# PumpSpark.net
KiCad netlist of a schematic drawn in EAGLE
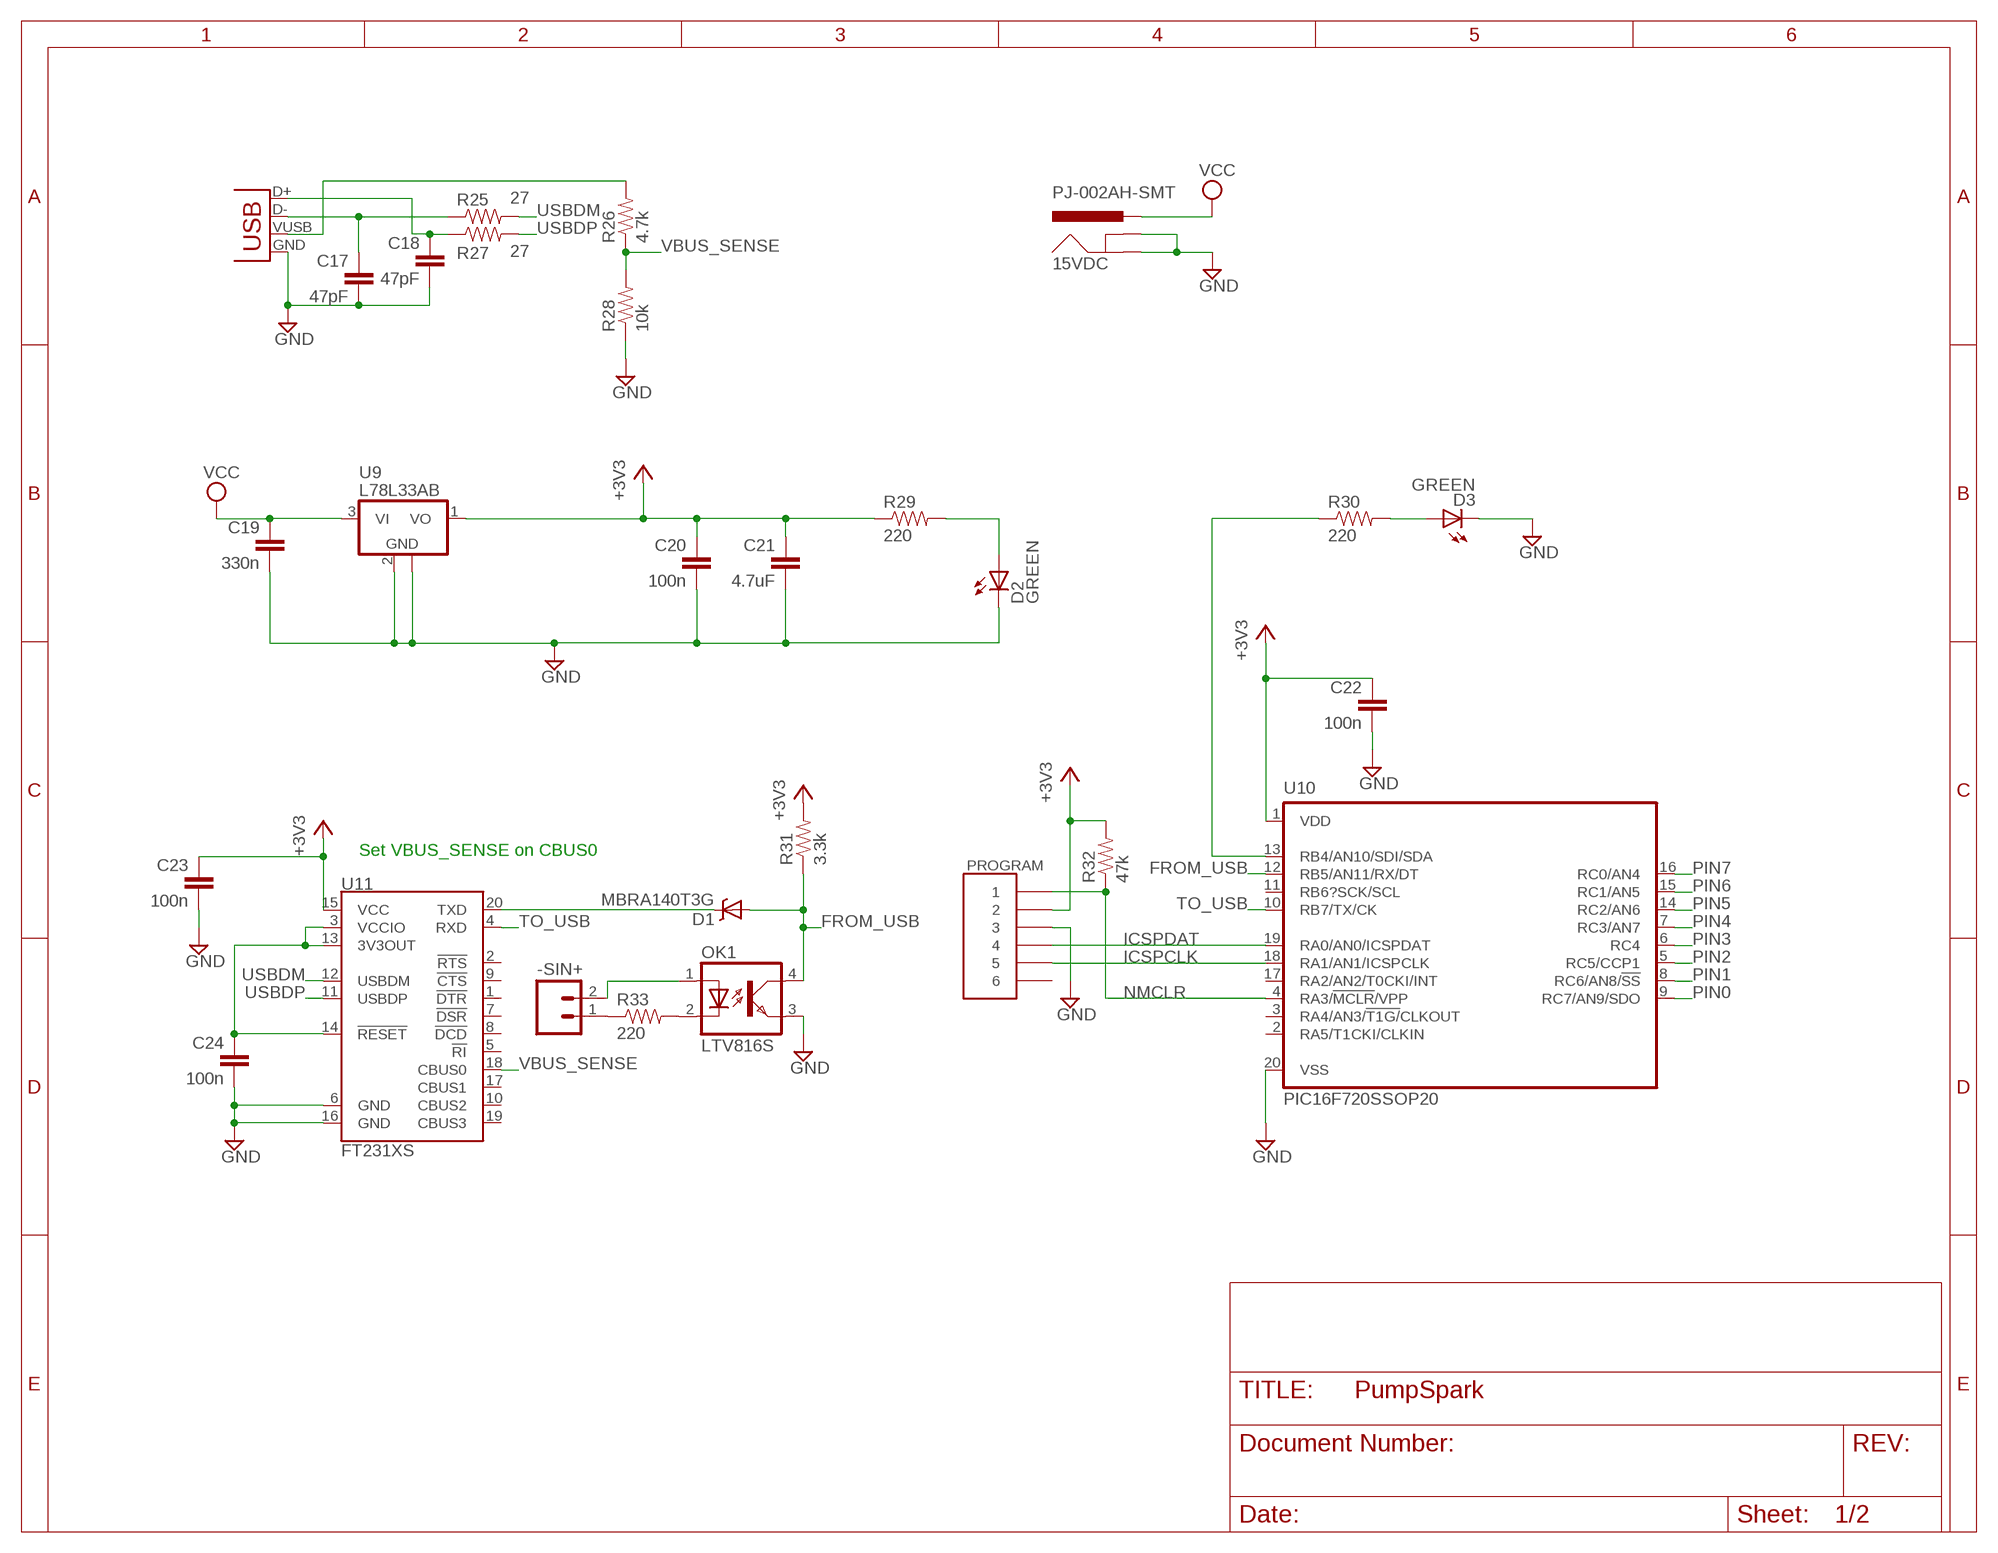
[diagram p0: schematic, sheet 1]
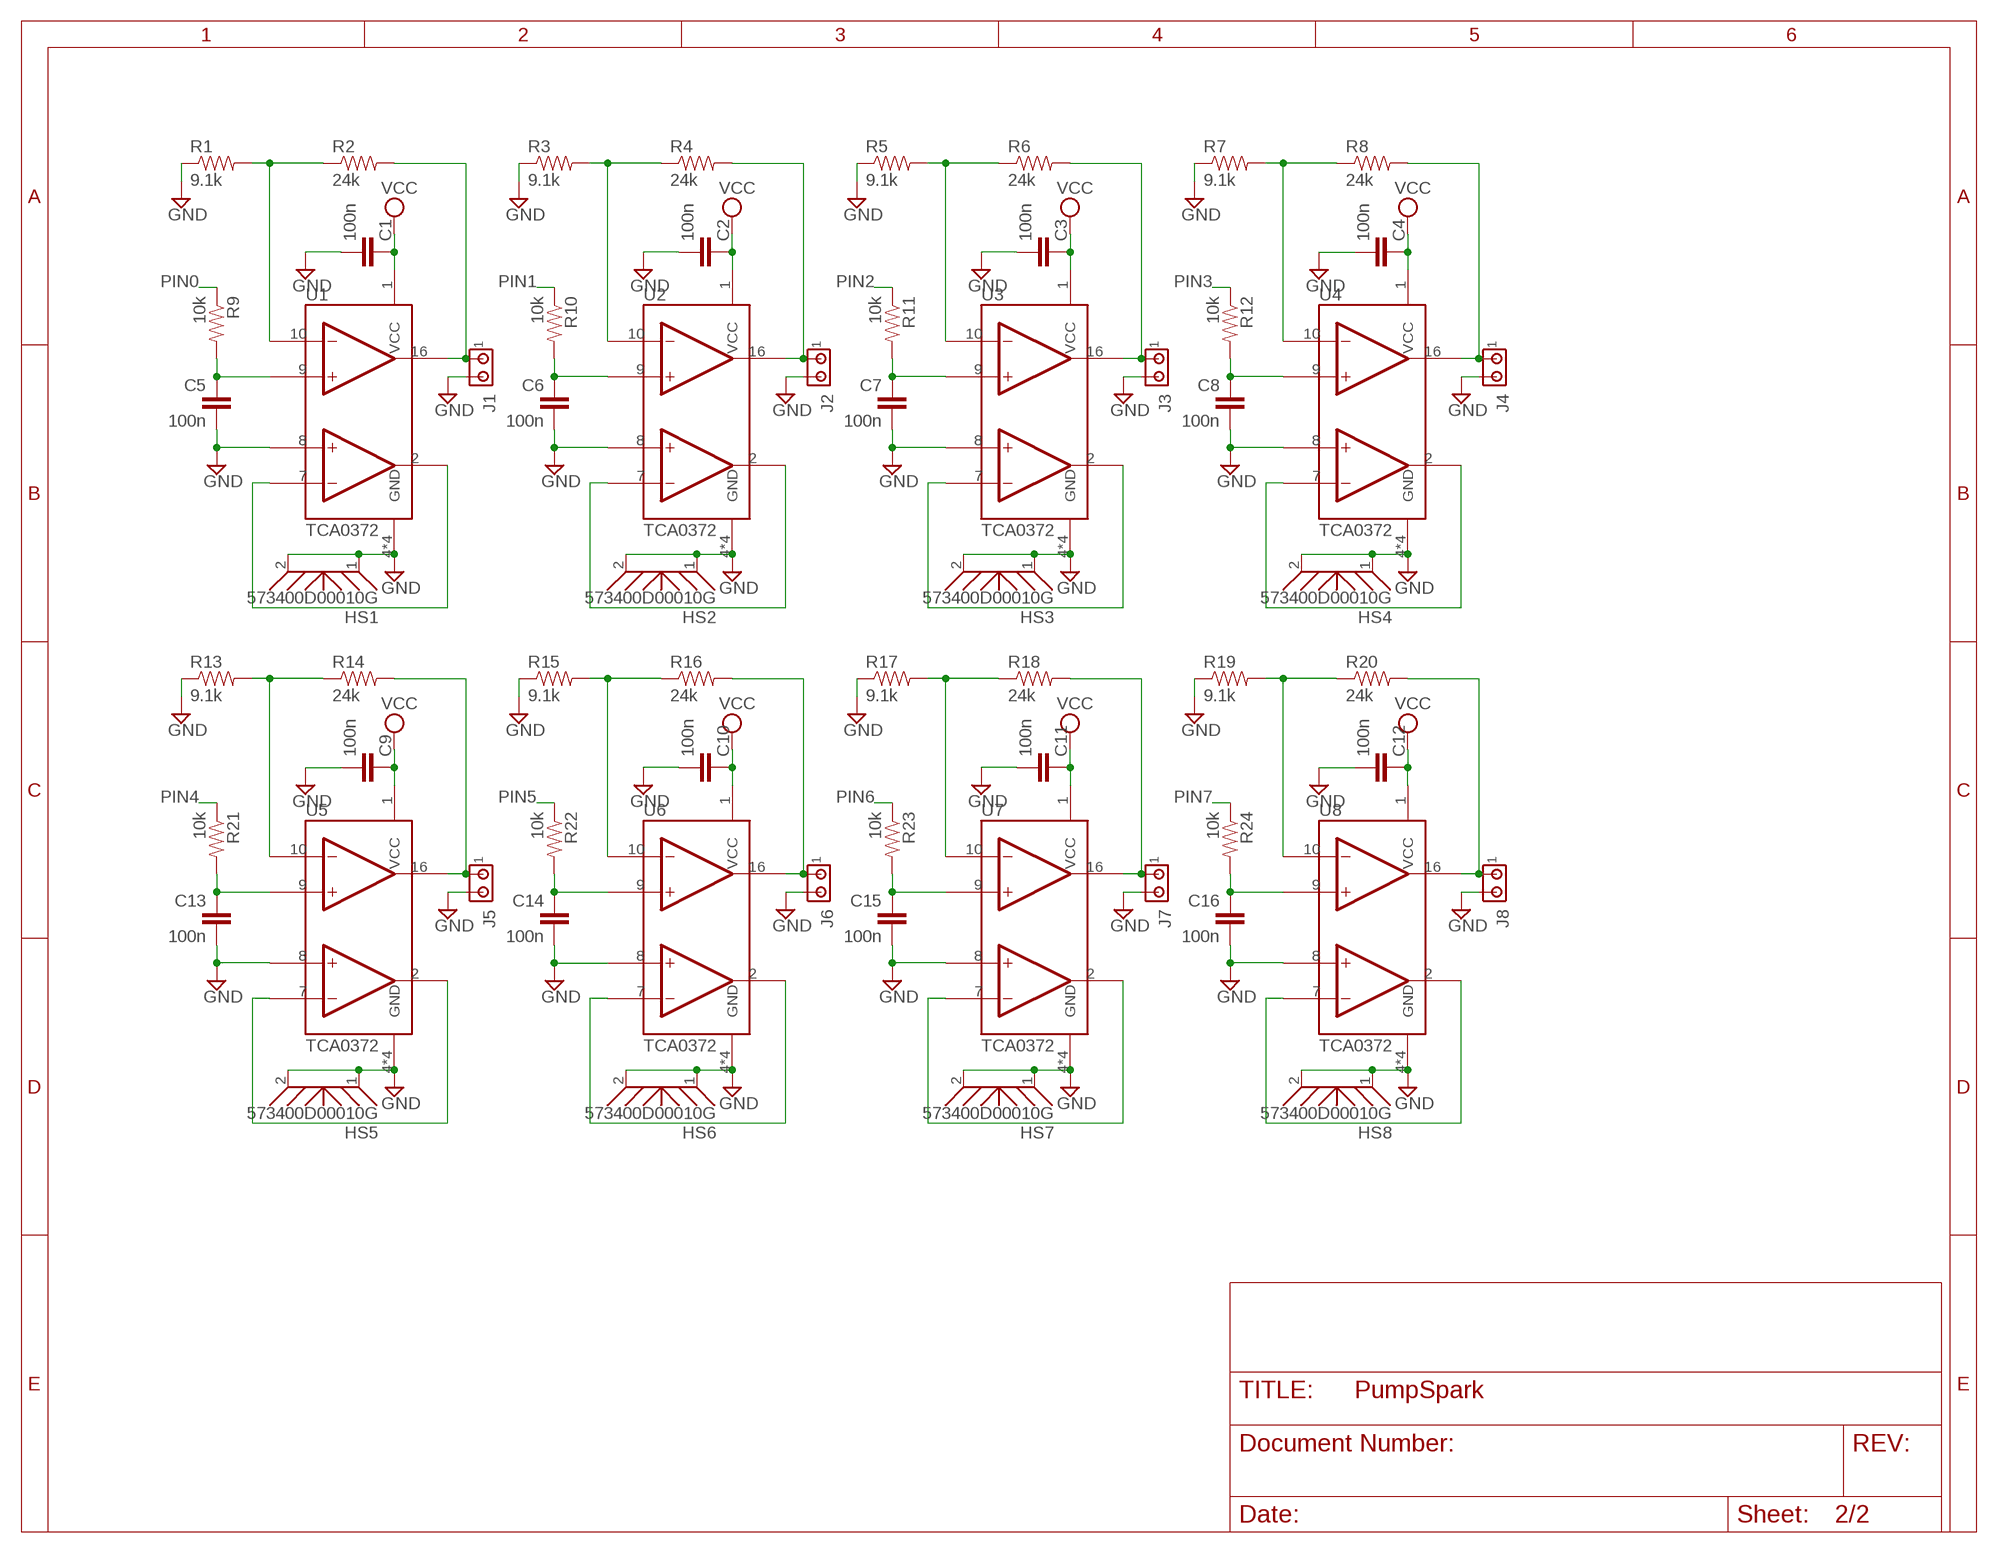
[diagram p1: schematic, sheet 2]

(export (version "E")
  (design (tool "Eeschema 10.0.6"))
  (components
    (comp (ref "-SIN+")
      (value "M02LOCK")
      (footprint "eagle-import:1X02_LOCK")
      (libsource (lib "eagle-import") (part "M02LOCK"))
    )
    (comp (ref "15VDC")
      (value "PJ-002AH-SMT")
      (footprint "eagle-import:POWER_JACK_SMD")
      (libsource (lib "eagle-import") (part "POWER_JACKSMD"))
    )
    (comp (ref "C17")
      (value "47pF")
      (footprint "eagle-import:0603-CAP")
      (libsource (lib "eagle-import") (part "CAP0603-CAP"))
    )
    (comp (ref "C18")
      (value "47pF")
      (footprint "eagle-import:0603-CAP")
      (libsource (lib "eagle-import") (part "CAP0603-CAP"))
    )
    (comp (ref "C19")
      (value "330n")
      (footprint "eagle-import:0603-CAP")
      (libsource (lib "eagle-import") (part "CAP0603-CAP"))
    )
    (comp (ref "C20")
      (value "100n")
      (footprint "eagle-import:0603-CAP")
      (libsource (lib "eagle-import") (part "CAP0603-CAP"))
    )
    (comp (ref "C21")
      (value "4.7uF")
      (footprint "eagle-import:0603-CAP")
      (libsource (lib "eagle-import") (part "CAP0603-CAP"))
    )
    (comp (ref "C22")
      (value "100n")
      (footprint "eagle-import:0603-CAP")
      (libsource (lib "eagle-import") (part "CAP0603-CAP"))
    )
    (comp (ref "C23")
      (value "100n")
      (footprint "eagle-import:0603-CAP")
      (libsource (lib "eagle-import") (part "CAP0603-CAP"))
    )
    (comp (ref "C24")
      (value "100n")
      (footprint "eagle-import:0603-CAP")
      (libsource (lib "eagle-import") (part "CAP0603-CAP"))
    )
    (comp (ref "D1")
      (value "MBRA140T3G")
      (footprint "eagle-import:SMA-DIODE")
      (libsource (lib "eagle-import") (part "DIODE-SCHOTTKY_"))
    )
    (comp (ref "D2")
      (value "GREEN")
      (footprint "eagle-import:LED-0603")
      (libsource (lib "eagle-import") (part "LED-GREEN0603"))
    )
    (comp (ref "D3")
      (value "GREEN")
      (footprint "eagle-import:LED-0603")
      (libsource (lib "eagle-import") (part "LED-GREEN0603"))
    )
    (comp (ref "OK1")
      (value "LTV816S")
      (footprint "eagle-import:SMD4")
      (libsource (lib "eagle-import") (part "LTV816S"))
    )
    (comp (ref "PROGRAM")
      (value "HEADER-6MOLEX-KK")
      (footprint "eagle-import:MOLEX-KK-HEADER-6")
      (libsource (lib "eagle-import") (part "HEADER-6MOLEX-KK"))
    )
    (comp (ref "R25")
      (value "27")
      (footprint "eagle-import:0603-RES")
      (libsource (lib "eagle-import") (part "RESISTOR0603-RES"))
    )
    (comp (ref "R26")
      (value "4.7k")
      (footprint "eagle-import:0603-RES")
      (libsource (lib "eagle-import") (part "RESISTOR0603-RES"))
    )
    (comp (ref "R27")
      (value "27")
      (footprint "eagle-import:0603-RES")
      (libsource (lib "eagle-import") (part "RESISTOR0603-RES"))
    )
    (comp (ref "R28")
      (value "10k")
      (footprint "eagle-import:0603-RES")
      (libsource (lib "eagle-import") (part "RESISTOR0603-RES"))
    )
    (comp (ref "R29")
      (value "220")
      (footprint "eagle-import:0603-RES")
      (libsource (lib "eagle-import") (part "RESISTOR0603-RES"))
    )
    (comp (ref "R30")
      (value "220")
      (footprint "eagle-import:0603-RES")
      (libsource (lib "eagle-import") (part "RESISTOR0603-RES"))
    )
    (comp (ref "R31")
      (value "3.3k")
      (footprint "eagle-import:0603-RES")
      (libsource (lib "eagle-import") (part "RESISTOR0603-RES"))
    )
    (comp (ref "R32")
      (value "47k")
      (footprint "eagle-import:0603-RES")
      (libsource (lib "eagle-import") (part "RESISTOR0603-RES"))
    )
    (comp (ref "R33")
      (value "220")
      (footprint "eagle-import:0603-RES")
      (libsource (lib "eagle-import") (part "RESISTOR0603-RES"))
    )
    (comp (ref "U9")
      (value "L78L33AB")
      (footprint "eagle-import:SOT89")
      (libsource (lib "eagle-import") (part "78LF05"))
    )
    (comp (ref "U10")
      (value "PIC16F720SSOP20")
      (footprint "eagle-import:SSOP20")
      (libsource (lib "eagle-import") (part "PIC16F720SSOP20"))
    )
    (comp (ref "U11")
      (value "FT231XS")
      (footprint "eagle-import:SSOP20_L")
      (libsource (lib "eagle-import") (part "FT231XS"))
    )
    (comp (ref "USB")
      (value "USB-B-S")
      (footprint "eagle-import:USB-B-SMT")
      (libsource (lib "eagle-import") (part "USB-B-S"))
    )
    (comp (ref "C1")
      (value "100n")
      (footprint "eagle-import:0603-CAP")
      (libsource (lib "eagle-import") (part "CAP0603-CAP"))
    )
    (comp (ref "C2")
      (value "100n")
      (footprint "eagle-import:0603-CAP")
      (libsource (lib "eagle-import") (part "CAP0603-CAP"))
    )
    (comp (ref "C3")
      (value "100n")
      (footprint "eagle-import:0603-CAP")
      (libsource (lib "eagle-import") (part "CAP0603-CAP"))
    )
    (comp (ref "C4")
      (value "100n")
      (footprint "eagle-import:0603-CAP")
      (libsource (lib "eagle-import") (part "CAP0603-CAP"))
    )
    (comp (ref "C5")
      (value "100n")
      (footprint "eagle-import:0603-CAP")
      (libsource (lib "eagle-import") (part "CAP0603-CAP"))
    )
    (comp (ref "C6")
      (value "100n")
      (footprint "eagle-import:0603-CAP")
      (libsource (lib "eagle-import") (part "CAP0603-CAP"))
    )
    (comp (ref "C7")
      (value "100n")
      (footprint "eagle-import:0603-CAP")
      (libsource (lib "eagle-import") (part "CAP0603-CAP"))
    )
    (comp (ref "C8")
      (value "100n")
      (footprint "eagle-import:0603-CAP")
      (libsource (lib "eagle-import") (part "CAP0603-CAP"))
    )
    (comp (ref "C9")
      (value "100n")
      (footprint "eagle-import:0603-CAP")
      (libsource (lib "eagle-import") (part "CAP0603-CAP"))
    )
    (comp (ref "C10")
      (value "100n")
      (footprint "eagle-import:0603-CAP")
      (libsource (lib "eagle-import") (part "CAP0603-CAP"))
    )
    (comp (ref "C11")
      (value "100n")
      (footprint "eagle-import:0603-CAP")
      (libsource (lib "eagle-import") (part "CAP0603-CAP"))
    )
    (comp (ref "C12")
      (value "100n")
      (footprint "eagle-import:0603-CAP")
      (libsource (lib "eagle-import") (part "CAP0603-CAP"))
    )
    (comp (ref "C13")
      (value "100n")
      (footprint "eagle-import:0603-CAP")
      (libsource (lib "eagle-import") (part "CAP0603-CAP"))
    )
    (comp (ref "C14")
      (value "100n")
      (footprint "eagle-import:0603-CAP")
      (libsource (lib "eagle-import") (part "CAP0603-CAP"))
    )
    (comp (ref "C15")
      (value "100n")
      (footprint "eagle-import:0603-CAP")
      (libsource (lib "eagle-import") (part "CAP0603-CAP"))
    )
    (comp (ref "C16")
      (value "100n")
      (footprint "eagle-import:0603-CAP")
      (libsource (lib "eagle-import") (part "CAP0603-CAP"))
    )
    (comp (ref "HS1")
      (value "573400D00010G")
      (footprint "eagle-import:573400D00010G")
      (libsource (lib "eagle-import") (part "573400D00010G"))
    )
    (comp (ref "HS2")
      (value "573400D00010G")
      (footprint "eagle-import:573400D00010G")
      (libsource (lib "eagle-import") (part "573400D00010G"))
    )
    (comp (ref "HS3")
      (value "573400D00010G")
      (footprint "eagle-import:573400D00010G")
      (libsource (lib "eagle-import") (part "573400D00010G"))
    )
    (comp (ref "HS4")
      (value "573400D00010G")
      (footprint "eagle-import:573400D00010G")
      (libsource (lib "eagle-import") (part "573400D00010G"))
    )
    (comp (ref "HS5")
      (value "573400D00010G")
      (footprint "eagle-import:573400D00010G")
      (libsource (lib "eagle-import") (part "573400D00010G"))
    )
    (comp (ref "HS6")
      (value "573400D00010G")
      (footprint "eagle-import:573400D00010G")
      (libsource (lib "eagle-import") (part "573400D00010G"))
    )
    (comp (ref "HS7")
      (value "573400D00010G")
      (footprint "eagle-import:573400D00010G")
      (libsource (lib "eagle-import") (part "573400D00010G"))
    )
    (comp (ref "HS8")
      (value "573400D00010G")
      (footprint "eagle-import:573400D00010G")
      (libsource (lib "eagle-import") (part "573400D00010G"))
    )
    (comp (ref "J1")
      (value "MTA02-100")
      (footprint "eagle-import:10X02MTA")
      (libsource (lib "eagle-import") (part "MTA02-100"))
    )
    (comp (ref "J2")
      (value "MTA02-100")
      (footprint "eagle-import:10X02MTA")
      (libsource (lib "eagle-import") (part "MTA02-100"))
    )
    (comp (ref "J3")
      (value "MTA02-100")
      (footprint "eagle-import:10X02MTA")
      (libsource (lib "eagle-import") (part "MTA02-100"))
    )
    (comp (ref "J4")
      (value "MTA02-100")
      (footprint "eagle-import:10X02MTA")
      (libsource (lib "eagle-import") (part "MTA02-100"))
    )
    (comp (ref "J5")
      (value "MTA02-100")
      (footprint "eagle-import:10X02MTA")
      (libsource (lib "eagle-import") (part "MTA02-100"))
    )
    (comp (ref "J6")
      (value "MTA02-100")
      (footprint "eagle-import:10X02MTA")
      (libsource (lib "eagle-import") (part "MTA02-100"))
    )
    (comp (ref "J7")
      (value "MTA02-100")
      (footprint "eagle-import:10X02MTA")
      (libsource (lib "eagle-import") (part "MTA02-100"))
    )
    (comp (ref "J8")
      (value "MTA02-100")
      (footprint "eagle-import:10X02MTA")
      (libsource (lib "eagle-import") (part "MTA02-100"))
    )
    (comp (ref "R1")
      (value "9.1k")
      (footprint "eagle-import:0603-RES")
      (libsource (lib "eagle-import") (part "RESISTOR0603-RES"))
    )
    (comp (ref "R2")
      (value "24k")
      (footprint "eagle-import:0603-RES")
      (libsource (lib "eagle-import") (part "RESISTOR0603-RES"))
    )
    (comp (ref "R3")
      (value "9.1k")
      (footprint "eagle-import:0603-RES")
      (libsource (lib "eagle-import") (part "RESISTOR0603-RES"))
    )
    (comp (ref "R4")
      (value "24k")
      (footprint "eagle-import:0603-RES")
      (libsource (lib "eagle-import") (part "RESISTOR0603-RES"))
    )
    (comp (ref "R5")
      (value "9.1k")
      (footprint "eagle-import:0603-RES")
      (libsource (lib "eagle-import") (part "RESISTOR0603-RES"))
    )
    (comp (ref "R6")
      (value "24k")
      (footprint "eagle-import:0603-RES")
      (libsource (lib "eagle-import") (part "RESISTOR0603-RES"))
    )
    (comp (ref "R7")
      (value "9.1k")
      (footprint "eagle-import:0603-RES")
      (libsource (lib "eagle-import") (part "RESISTOR0603-RES"))
    )
    (comp (ref "R8")
      (value "24k")
      (footprint "eagle-import:0603-RES")
      (libsource (lib "eagle-import") (part "RESISTOR0603-RES"))
    )
    (comp (ref "R9")
      (value "10k")
      (footprint "eagle-import:0603-RES")
      (libsource (lib "eagle-import") (part "RESISTOR0603-RES"))
    )
    (comp (ref "R10")
      (value "10k")
      (footprint "eagle-import:0603-RES")
      (libsource (lib "eagle-import") (part "RESISTOR0603-RES"))
    )
    (comp (ref "R11")
      (value "10k")
      (footprint "eagle-import:0603-RES")
      (libsource (lib "eagle-import") (part "RESISTOR0603-RES"))
    )
    (comp (ref "R12")
      (value "10k")
      (footprint "eagle-import:0603-RES")
      (libsource (lib "eagle-import") (part "RESISTOR0603-RES"))
    )
    (comp (ref "R13")
      (value "9.1k")
      (footprint "eagle-import:0603-RES")
      (libsource (lib "eagle-import") (part "RESISTOR0603-RES"))
    )
    (comp (ref "R14")
      (value "24k")
      (footprint "eagle-import:0603-RES")
      (libsource (lib "eagle-import") (part "RESISTOR0603-RES"))
    )
    (comp (ref "R15")
      (value "9.1k")
      (footprint "eagle-import:0603-RES")
      (libsource (lib "eagle-import") (part "RESISTOR0603-RES"))
    )
    (comp (ref "R16")
      (value "24k")
      (footprint "eagle-import:0603-RES")
      (libsource (lib "eagle-import") (part "RESISTOR0603-RES"))
    )
    (comp (ref "R17")
      (value "9.1k")
      (footprint "eagle-import:0603-RES")
      (libsource (lib "eagle-import") (part "RESISTOR0603-RES"))
    )
    (comp (ref "R18")
      (value "24k")
      (footprint "eagle-import:0603-RES")
      (libsource (lib "eagle-import") (part "RESISTOR0603-RES"))
    )
    (comp (ref "R19")
      (value "9.1k")
      (footprint "eagle-import:0603-RES")
      (libsource (lib "eagle-import") (part "RESISTOR0603-RES"))
    )
    (comp (ref "R20")
      (value "24k")
      (footprint "eagle-import:0603-RES")
      (libsource (lib "eagle-import") (part "RESISTOR0603-RES"))
    )
    (comp (ref "R21")
      (value "10k")
      (footprint "eagle-import:0603-RES")
      (libsource (lib "eagle-import") (part "RESISTOR0603-RES"))
    )
    (comp (ref "R22")
      (value "10k")
      (footprint "eagle-import:0603-RES")
      (libsource (lib "eagle-import") (part "RESISTOR0603-RES"))
    )
    (comp (ref "R23")
      (value "10k")
      (footprint "eagle-import:0603-RES")
      (libsource (lib "eagle-import") (part "RESISTOR0603-RES"))
    )
    (comp (ref "R24")
      (value "10k")
      (footprint "eagle-import:0603-RES")
      (libsource (lib "eagle-import") (part "RESISTOR0603-RES"))
    )
    (comp (ref "U1")
      (value "TCA0372")
      (footprint "eagle-import:SO16W")
      (libsource (lib "eagle-import") (part "TCA0372"))
    )
    (comp (ref "U2")
      (value "TCA0372")
      (footprint "eagle-import:SO16W")
      (libsource (lib "eagle-import") (part "TCA0372"))
    )
    (comp (ref "U3")
      (value "TCA0372")
      (footprint "eagle-import:SO16W")
      (libsource (lib "eagle-import") (part "TCA0372"))
    )
    (comp (ref "U4")
      (value "TCA0372")
      (footprint "eagle-import:SO16W")
      (libsource (lib "eagle-import") (part "TCA0372"))
    )
    (comp (ref "U5")
      (value "TCA0372")
      (footprint "eagle-import:SO16W")
      (libsource (lib "eagle-import") (part "TCA0372"))
    )
    (comp (ref "U6")
      (value "TCA0372")
      (footprint "eagle-import:SO16W")
      (libsource (lib "eagle-import") (part "TCA0372"))
    )
    (comp (ref "U7")
      (value "TCA0372")
      (footprint "eagle-import:SO16W")
      (libsource (lib "eagle-import") (part "TCA0372"))
    )
    (comp (ref "U8")
      (value "TCA0372")
      (footprint "eagle-import:SO16W")
      (libsource (lib "eagle-import") (part "TCA0372"))
    )
  )
  (nets
    (net (code "1") (name "+3V3") (class "Default")
      (node (ref "C20") (pin "1") (pinfunction "1_1") (pintype "passive"))
      (node (ref "C21") (pin "1") (pinfunction "1_1") (pintype "passive"))
      (node (ref "C22") (pin "1") (pinfunction "1_1") (pintype "passive"))
      (node (ref "C23") (pin "1") (pinfunction "1_1") (pintype "passive"))
      (node (ref "PROGRAM") (pin "2") (pinfunction "2_2") (pintype "bidirectional"))
      (node (ref "R29") (pin "1") (pinfunction "1_1") (pintype "passive"))
      (node (ref "R31") (pin "2") (pinfunction "2_2") (pintype "passive"))
      (node (ref "R32") (pin "2") (pinfunction "2_2") (pintype "passive"))
      (node (ref "U10") (pin "1") (pinfunction "VDD_1") (pintype "power_in"))
      (node (ref "U11") (pin "15") (pinfunction "VCC_15") (pintype "bidirectional"))
      (node (ref "U9") (pin "1") (pinfunction "VO_1") (pintype "passive"))
    )
    (net (code "2") (name "FROM_USB") (class "Default")
      (node (ref "D1") (pin "A") (pinfunction "A_A") (pintype "passive"))
      (node (ref "OK1") (pin "4") (pinfunction "COL_4") (pintype "passive"))
      (node (ref "R31") (pin "1") (pinfunction "1_1") (pintype "passive"))
      (node (ref "U10") (pin "12") (pinfunction "RB5/AN11/RX/DT_12") (pintype "bidirectional"))
    )
    (net (code "3") (name "GND") (class "Default")
      (node (ref "15VDC") (pin "GND") (pinfunction "GNDBREAK_GND") (pintype "bidirectional"))
      (node (ref "15VDC") (pin "P$4") (pinfunction "GND_P$4") (pintype "bidirectional"))
      (node (ref "C1") (pin "2") (pinfunction "2_2") (pintype "passive"))
      (node (ref "C10") (pin "2") (pinfunction "2_2") (pintype "passive"))
      (node (ref "C11") (pin "2") (pinfunction "2_2") (pintype "passive"))
      (node (ref "C12") (pin "2") (pinfunction "2_2") (pintype "passive"))
      (node (ref "C13") (pin "2") (pinfunction "2_2") (pintype "passive"))
      (node (ref "C14") (pin "2") (pinfunction "2_2") (pintype "passive"))
      (node (ref "C15") (pin "2") (pinfunction "2_2") (pintype "passive"))
      (node (ref "C16") (pin "2") (pinfunction "2_2") (pintype "passive"))
      (node (ref "C17") (pin "2") (pinfunction "2_2") (pintype "passive"))
      (node (ref "C18") (pin "2") (pinfunction "2_2") (pintype "passive"))
      (node (ref "C19") (pin "2") (pinfunction "2_2") (pintype "passive"))
      (node (ref "C2") (pin "2") (pinfunction "2_2") (pintype "passive"))
      (node (ref "C20") (pin "2") (pinfunction "2_2") (pintype "passive"))
      (node (ref "C21") (pin "2") (pinfunction "2_2") (pintype "passive"))
      (node (ref "C22") (pin "2") (pinfunction "2_2") (pintype "passive"))
      (node (ref "C23") (pin "2") (pinfunction "2_2") (pintype "passive"))
      (node (ref "C24") (pin "2") (pinfunction "2_2") (pintype "passive"))
      (node (ref "C3") (pin "2") (pinfunction "2_2") (pintype "passive"))
      (node (ref "C4") (pin "2") (pinfunction "2_2") (pintype "passive"))
      (node (ref "C5") (pin "2") (pinfunction "2_2") (pintype "passive"))
      (node (ref "C6") (pin "2") (pinfunction "2_2") (pintype "passive"))
      (node (ref "C7") (pin "2") (pinfunction "2_2") (pintype "passive"))
      (node (ref "C8") (pin "2") (pinfunction "2_2") (pintype "passive"))
      (node (ref "C9") (pin "2") (pinfunction "2_2") (pintype "passive"))
      (node (ref "D2") (pin "C") (pinfunction "C_C") (pintype "passive"))
      (node (ref "D3") (pin "C") (pinfunction "C_C") (pintype "passive"))
      (node (ref "HS1") (pin "1") (pinfunction "LEFT_1") (pintype "passive"))
      (node (ref "HS1") (pin "2") (pinfunction "RIGHT_2") (pintype "passive"))
      (node (ref "HS2") (pin "1") (pinfunction "LEFT_1") (pintype "passive"))
      (node (ref "HS2") (pin "2") (pinfunction "RIGHT_2") (pintype "passive"))
      (node (ref "HS3") (pin "1") (pinfunction "LEFT_1") (pintype "passive"))
      (node (ref "HS3") (pin "2") (pinfunction "RIGHT_2") (pintype "passive"))
      (node (ref "HS4") (pin "1") (pinfunction "LEFT_1") (pintype "passive"))
      (node (ref "HS4") (pin "2") (pinfunction "RIGHT_2") (pintype "passive"))
      (node (ref "HS5") (pin "1") (pinfunction "LEFT_1") (pintype "passive"))
      (node (ref "HS5") (pin "2") (pinfunction "RIGHT_2") (pintype "passive"))
      (node (ref "HS6") (pin "1") (pinfunction "LEFT_1") (pintype "passive"))
      (node (ref "HS6") (pin "2") (pinfunction "RIGHT_2") (pintype "passive"))
      (node (ref "HS7") (pin "1") (pinfunction "LEFT_1") (pintype "passive"))
      (node (ref "HS7") (pin "2") (pinfunction "RIGHT_2") (pintype "passive"))
      (node (ref "HS8") (pin "1") (pinfunction "LEFT_1") (pintype "passive"))
      (node (ref "HS8") (pin "2") (pinfunction "RIGHT_2") (pintype "passive"))
      (node (ref "J1") (pin "2") (pinfunction "2_2") (pintype "passive"))
      (node (ref "J2") (pin "2") (pinfunction "2_2") (pintype "passive"))
      (node (ref "J3") (pin "2") (pinfunction "2_2") (pintype "passive"))
      (node (ref "J4") (pin "2") (pinfunction "2_2") (pintype "passive"))
      (node (ref "J5") (pin "2") (pinfunction "2_2") (pintype "passive"))
      (node (ref "J6") (pin "2") (pinfunction "2_2") (pintype "passive"))
      (node (ref "J7") (pin "2") (pinfunction "2_2") (pintype "passive"))
      (node (ref "J8") (pin "2") (pinfunction "2_2") (pintype "passive"))
      (node (ref "OK1") (pin "3") (pinfunction "EMIT_3") (pintype "passive"))
      (node (ref "PROGRAM") (pin "3") (pinfunction "3_3") (pintype "bidirectional"))
      (node (ref "R1") (pin "1") (pinfunction "1_1") (pintype "passive"))
      (node (ref "R13") (pin "1") (pinfunction "1_1") (pintype "passive"))
      (node (ref "R15") (pin "1") (pinfunction "1_1") (pintype "passive"))
      (node (ref "R17") (pin "1") (pinfunction "1_1") (pintype "passive"))
      (node (ref "R19") (pin "1") (pinfunction "1_1") (pintype "passive"))
      (node (ref "R28") (pin "1") (pinfunction "1_1") (pintype "passive"))
      (node (ref "R3") (pin "1") (pinfunction "1_1") (pintype "passive"))
      (node (ref "R5") (pin "1") (pinfunction "1_1") (pintype "passive"))
      (node (ref "R7") (pin "1") (pinfunction "1_1") (pintype "passive"))
      (node (ref "U1") (pin "12") (pinfunction "GND_12") (pintype "power_in"))
      (node (ref "U1") (pin "13") (pinfunction "GND_13") (pintype "power_in"))
      (node (ref "U1") (pin "4") (pinfunction "GND_4") (pintype "power_in"))
      (node (ref "U1") (pin "5") (pinfunction "GND_5") (pintype "power_in"))
      (node (ref "U1") (pin "8") (pinfunction "+INB_8") (pintype "input"))
      (node (ref "U10") (pin "20") (pinfunction "VSS_20") (pintype "power_in"))
      (node (ref "U11") (pin "16") (pinfunction "GND_16") (pintype "bidirectional"))
      (node (ref "U11") (pin "6") (pinfunction "GND_6") (pintype "bidirectional"))
      (node (ref "U2") (pin "12") (pinfunction "GND_12") (pintype "power_in"))
      (node (ref "U2") (pin "13") (pinfunction "GND_13") (pintype "power_in"))
      (node (ref "U2") (pin "4") (pinfunction "GND_4") (pintype "power_in"))
      (node (ref "U2") (pin "5") (pinfunction "GND_5") (pintype "power_in"))
      (node (ref "U2") (pin "8") (pinfunction "+INB_8") (pintype "input"))
      (node (ref "U3") (pin "12") (pinfunction "GND_12") (pintype "power_in"))
      (node (ref "U3") (pin "13") (pinfunction "GND_13") (pintype "power_in"))
      (node (ref "U3") (pin "4") (pinfunction "GND_4") (pintype "power_in"))
      (node (ref "U3") (pin "5") (pinfunction "GND_5") (pintype "power_in"))
      (node (ref "U3") (pin "8") (pinfunction "+INB_8") (pintype "input"))
      (node (ref "U4") (pin "12") (pinfunction "GND_12") (pintype "power_in"))
      (node (ref "U4") (pin "13") (pinfunction "GND_13") (pintype "power_in"))
      (node (ref "U4") (pin "4") (pinfunction "GND_4") (pintype "power_in"))
      (node (ref "U4") (pin "5") (pinfunction "GND_5") (pintype "power_in"))
      (node (ref "U4") (pin "8") (pinfunction "+INB_8") (pintype "input"))
      (node (ref "U5") (pin "12") (pinfunction "GND_12") (pintype "power_in"))
      (node (ref "U5") (pin "13") (pinfunction "GND_13") (pintype "power_in"))
      (node (ref "U5") (pin "4") (pinfunction "GND_4") (pintype "power_in"))
      (node (ref "U5") (pin "5") (pinfunction "GND_5") (pintype "power_in"))
      (node (ref "U5") (pin "8") (pinfunction "+INB_8") (pintype "input"))
      (node (ref "U6") (pin "12") (pinfunction "GND_12") (pintype "power_in"))
      (node (ref "U6") (pin "13") (pinfunction "GND_13") (pintype "power_in"))
      (node (ref "U6") (pin "4") (pinfunction "GND_4") (pintype "power_in"))
      (node (ref "U6") (pin "5") (pinfunction "GND_5") (pintype "power_in"))
      (node (ref "U6") (pin "8") (pinfunction "+INB_8") (pintype "input"))
      (node (ref "U7") (pin "12") (pinfunction "GND_12") (pintype "power_in"))
      (node (ref "U7") (pin "13") (pinfunction "GND_13") (pintype "power_in"))
      (node (ref "U7") (pin "4") (pinfunction "GND_4") (pintype "power_in"))
      (node (ref "U7") (pin "5") (pinfunction "GND_5") (pintype "power_in"))
      (node (ref "U7") (pin "8") (pinfunction "+INB_8") (pintype "input"))
      (node (ref "U8") (pin "12") (pinfunction "GND_12") (pintype "power_in"))
      (node (ref "U8") (pin "13") (pinfunction "GND_13") (pintype "power_in"))
      (node (ref "U8") (pin "4") (pinfunction "GND_4") (pintype "power_in"))
      (node (ref "U8") (pin "5") (pinfunction "GND_5") (pintype "power_in"))
      (node (ref "U8") (pin "8") (pinfunction "+INB_8") (pintype "input"))
      (node (ref "U9") (pin "2") (pinfunction "GND_2") (pintype "passive"))
      (node (ref "U9") (pin "2@1") (pinfunction "GND_2@1") (pintype "passive"))
      (node (ref "USB") (pin "GND") (pinfunction "GND_GND") (pintype "bidirectional"))
    )
    (net (code "4") (name "ICSPCLK") (class "Default")
      (node (ref "PROGRAM") (pin "5") (pinfunction "5_5") (pintype "bidirectional"))
      (node (ref "U10") (pin "18") (pinfunction "RA1/AN1/ICSPCLK_18") (pintype "bidirectional"))
    )
    (net (code "5") (name "ICSPDAT") (class "Default")
      (node (ref "PROGRAM") (pin "4") (pinfunction "4_4") (pintype "bidirectional"))
      (node (ref "U10") (pin "19") (pinfunction "RA0/AN0/ICSPDAT_19") (pintype "bidirectional"))
    )
    (net (code "6") (name "NMCLR") (class "Default")
      (node (ref "PROGRAM") (pin "1") (pinfunction "1_1") (pintype "bidirectional"))
      (node (ref "R32") (pin "1") (pinfunction "1_1") (pintype "passive"))
      (node (ref "U10") (pin "4") (pinfunction "RA3/~{MCLR}/VPP_4") (pintype "bidirectional"))
    )
    (net (code "7") (name "Net-(-SIN+-Pad1)") (class "Default")
      (node (ref "-SIN+") (pin "1") (pinfunction "1_1") (pintype "passive"))
      (node (ref "R33") (pin "1") (pinfunction "1_1") (pintype "passive"))
    )
    (net (code "8") (name "Net-(C17-Pad1)") (class "Default")
      (node (ref "C17") (pin "1") (pinfunction "1_1") (pintype "passive"))
      (node (ref "R25") (pin "1") (pinfunction "1_1") (pintype "passive"))
      (node (ref "USB") (pin "D-") (pinfunction "D-_D-") (pintype "bidirectional"))
    )
    (net (code "9") (name "Net-(C18-Pad1)") (class "Default")
      (node (ref "C18") (pin "1") (pinfunction "1_1") (pintype "passive"))
      (node (ref "R27") (pin "1") (pinfunction "1_1") (pintype "passive"))
      (node (ref "USB") (pin "D+") (pinfunction "D+_D+") (pintype "bidirectional"))
    )
    (net (code "10") (name "Net-(D2-PadA)") (class "Default")
      (node (ref "D2") (pin "A") (pinfunction "A_A") (pintype "passive"))
      (node (ref "R29") (pin "2") (pinfunction "2_2") (pintype "passive"))
    )
    (net (code "11") (name "Net-(D3-PadA)") (class "Default")
      (node (ref "D3") (pin "A") (pinfunction "A_A") (pintype "passive"))
      (node (ref "R30") (pin "2") (pinfunction "2_2") (pintype "passive"))
    )
    (net (code "12") (name "Net-(OK1-A)") (class "Default")
      (node (ref "-SIN+") (pin "2") (pinfunction "2_2") (pintype "passive"))
      (node (ref "OK1") (pin "1") (pinfunction "A_1") (pintype "passive"))
    )
    (net (code "13") (name "Net-(OK1-C)") (class "Default")
      (node (ref "OK1") (pin "2") (pinfunction "C_2") (pintype "passive"))
      (node (ref "R33") (pin "2") (pinfunction "2_2") (pintype "passive"))
    )
    (net (code "14") (name "Net-(U1-+INA)") (class "Default")
      (node (ref "C5") (pin "1") (pinfunction "1_1") (pintype "passive"))
      (node (ref "R9") (pin "2") (pinfunction "2_2") (pintype "passive"))
      (node (ref "U1") (pin "9") (pinfunction "+INA_9") (pintype "input"))
    )
    (net (code "15") (name "Net-(U1--INA)") (class "Default")
      (node (ref "R1") (pin "2") (pinfunction "2_2") (pintype "passive"))
      (node (ref "R2") (pin "1") (pinfunction "1_1") (pintype "passive"))
      (node (ref "U1") (pin "10") (pinfunction "-INA_10") (pintype "input"))
    )
    (net (code "16") (name "Net-(U1--INB)") (class "Default")
      (node (ref "U1") (pin "2") (pinfunction "OUTB_2") (pintype "output"))
      (node (ref "U1") (pin "7") (pinfunction "-INB_7") (pintype "input"))
    )
    (net (code "17") (name "Net-(U1-OUTA)") (class "Default")
      (node (ref "J1") (pin "1") (pinfunction "1_1") (pintype "passive"))
      (node (ref "R2") (pin "2") (pinfunction "2_2") (pintype "passive"))
      (node (ref "U1") (pin "16") (pinfunction "OUTA_16") (pintype "output"))
    )
    (net (code "18") (name "Net-(U2-+INA)") (class "Default")
      (node (ref "C6") (pin "1") (pinfunction "1_1") (pintype "passive"))
      (node (ref "R10") (pin "2") (pinfunction "2_2") (pintype "passive"))
      (node (ref "U2") (pin "9") (pinfunction "+INA_9") (pintype "input"))
    )
    (net (code "19") (name "Net-(U2--INA)") (class "Default")
      (node (ref "R3") (pin "2") (pinfunction "2_2") (pintype "passive"))
      (node (ref "R4") (pin "1") (pinfunction "1_1") (pintype "passive"))
      (node (ref "U2") (pin "10") (pinfunction "-INA_10") (pintype "input"))
    )
    (net (code "20") (name "Net-(U2--INB)") (class "Default")
      (node (ref "U2") (pin "2") (pinfunction "OUTB_2") (pintype "output"))
      (node (ref "U2") (pin "7") (pinfunction "-INB_7") (pintype "input"))
    )
    (net (code "21") (name "Net-(U2-OUTA)") (class "Default")
      (node (ref "J2") (pin "1") (pinfunction "1_1") (pintype "passive"))
      (node (ref "R4") (pin "2") (pinfunction "2_2") (pintype "passive"))
      (node (ref "U2") (pin "16") (pinfunction "OUTA_16") (pintype "output"))
    )
    (net (code "22") (name "Net-(U3-+INA)") (class "Default")
      (node (ref "C7") (pin "1") (pinfunction "1_1") (pintype "passive"))
      (node (ref "R11") (pin "2") (pinfunction "2_2") (pintype "passive"))
      (node (ref "U3") (pin "9") (pinfunction "+INA_9") (pintype "input"))
    )
    (net (code "23") (name "Net-(U3--INA)") (class "Default")
      (node (ref "R5") (pin "2") (pinfunction "2_2") (pintype "passive"))
      (node (ref "R6") (pin "1") (pinfunction "1_1") (pintype "passive"))
      (node (ref "U3") (pin "10") (pinfunction "-INA_10") (pintype "input"))
    )
    (net (code "24") (name "Net-(U3--INB)") (class "Default")
      (node (ref "U3") (pin "2") (pinfunction "OUTB_2") (pintype "output"))
      (node (ref "U3") (pin "7") (pinfunction "-INB_7") (pintype "input"))
    )
    (net (code "25") (name "Net-(U3-OUTA)") (class "Default")
      (node (ref "J3") (pin "1") (pinfunction "1_1") (pintype "passive"))
      (node (ref "R6") (pin "2") (pinfunction "2_2") (pintype "passive"))
      (node (ref "U3") (pin "16") (pinfunction "OUTA_16") (pintype "output"))
    )
    (net (code "26") (name "Net-(U4-+INA)") (class "Default")
      (node (ref "C8") (pin "1") (pinfunction "1_1") (pintype "passive"))
      (node (ref "R12") (pin "2") (pinfunction "2_2") (pintype "passive"))
      (node (ref "U4") (pin "9") (pinfunction "+INA_9") (pintype "input"))
    )
    (net (code "27") (name "Net-(U4--INA)") (class "Default")
      (node (ref "R7") (pin "2") (pinfunction "2_2") (pintype "passive"))
      (node (ref "R8") (pin "1") (pinfunction "1_1") (pintype "passive"))
      (node (ref "U4") (pin "10") (pinfunction "-INA_10") (pintype "input"))
    )
    (net (code "28") (name "Net-(U4--INB)") (class "Default")
      (node (ref "U4") (pin "2") (pinfunction "OUTB_2") (pintype "output"))
      (node (ref "U4") (pin "7") (pinfunction "-INB_7") (pintype "input"))
    )
    (net (code "29") (name "Net-(U4-OUTA)") (class "Default")
      (node (ref "J4") (pin "1") (pinfunction "1_1") (pintype "passive"))
      (node (ref "R8") (pin "2") (pinfunction "2_2") (pintype "passive"))
      (node (ref "U4") (pin "16") (pinfunction "OUTA_16") (pintype "output"))
    )
    (net (code "30") (name "Net-(U5-+INA)") (class "Default")
      (node (ref "C13") (pin "1") (pinfunction "1_1") (pintype "passive"))
      (node (ref "R21") (pin "2") (pinfunction "2_2") (pintype "passive"))
      (node (ref "U5") (pin "9") (pinfunction "+INA_9") (pintype "input"))
    )
    (net (code "31") (name "Net-(U5--INA)") (class "Default")
      (node (ref "R13") (pin "2") (pinfunction "2_2") (pintype "passive"))
      (node (ref "R14") (pin "1") (pinfunction "1_1") (pintype "passive"))
      (node (ref "U5") (pin "10") (pinfunction "-INA_10") (pintype "input"))
    )
    (net (code "32") (name "Net-(U5--INB)") (class "Default")
      (node (ref "U5") (pin "2") (pinfunction "OUTB_2") (pintype "output"))
      (node (ref "U5") (pin "7") (pinfunction "-INB_7") (pintype "input"))
    )
    (net (code "33") (name "Net-(U5-OUTA)") (class "Default")
      (node (ref "J5") (pin "1") (pinfunction "1_1") (pintype "passive"))
      (node (ref "R14") (pin "2") (pinfunction "2_2") (pintype "passive"))
      (node (ref "U5") (pin "16") (pinfunction "OUTA_16") (pintype "output"))
    )
    (net (code "34") (name "Net-(U6-+INA)") (class "Default")
      (node (ref "C14") (pin "1") (pinfunction "1_1") (pintype "passive"))
      (node (ref "R22") (pin "2") (pinfunction "2_2") (pintype "passive"))
      (node (ref "U6") (pin "9") (pinfunction "+INA_9") (pintype "input"))
    )
    (net (code "35") (name "Net-(U6--INA)") (class "Default")
      (node (ref "R15") (pin "2") (pinfunction "2_2") (pintype "passive"))
      (node (ref "R16") (pin "1") (pinfunction "1_1") (pintype "passive"))
      (node (ref "U6") (pin "10") (pinfunction "-INA_10") (pintype "input"))
    )
    (net (code "36") (name "Net-(U6--INB)") (class "Default")
      (node (ref "U6") (pin "2") (pinfunction "OUTB_2") (pintype "output"))
      (node (ref "U6") (pin "7") (pinfunction "-INB_7") (pintype "input"))
    )
    (net (code "37") (name "Net-(U6-OUTA)") (class "Default")
      (node (ref "J6") (pin "1") (pinfunction "1_1") (pintype "passive"))
      (node (ref "R16") (pin "2") (pinfunction "2_2") (pintype "passive"))
      (node (ref "U6") (pin "16") (pinfunction "OUTA_16") (pintype "output"))
    )
    (net (code "38") (name "Net-(U7-+INA)") (class "Default")
      (node (ref "C15") (pin "1") (pinfunction "1_1") (pintype "passive"))
      (node (ref "R23") (pin "2") (pinfunction "2_2") (pintype "passive"))
      (node (ref "U7") (pin "9") (pinfunction "+INA_9") (pintype "input"))
    )
    (net (code "39") (name "Net-(U7--INA)") (class "Default")
      (node (ref "R17") (pin "2") (pinfunction "2_2") (pintype "passive"))
      (node (ref "R18") (pin "1") (pinfunction "1_1") (pintype "passive"))
      (node (ref "U7") (pin "10") (pinfunction "-INA_10") (pintype "input"))
    )
    (net (code "40") (name "Net-(U7--INB)") (class "Default")
      (node (ref "U7") (pin "2") (pinfunction "OUTB_2") (pintype "output"))
      (node (ref "U7") (pin "7") (pinfunction "-INB_7") (pintype "input"))
    )
    (net (code "41") (name "Net-(U7-OUTA)") (class "Default")
      (node (ref "J7") (pin "1") (pinfunction "1_1") (pintype "passive"))
      (node (ref "R18") (pin "2") (pinfunction "2_2") (pintype "passive"))
      (node (ref "U7") (pin "16") (pinfunction "OUTA_16") (pintype "output"))
    )
    (net (code "42") (name "Net-(U8-+INA)") (class "Default")
      (node (ref "C16") (pin "1") (pinfunction "1_1") (pintype "passive"))
      (node (ref "R24") (pin "2") (pinfunction "2_2") (pintype "passive"))
      (node (ref "U8") (pin "9") (pinfunction "+INA_9") (pintype "input"))
    )
    (net (code "43") (name "Net-(U8--INA)") (class "Default")
      (node (ref "R19") (pin "2") (pinfunction "2_2") (pintype "passive"))
      (node (ref "R20") (pin "1") (pinfunction "1_1") (pintype "passive"))
      (node (ref "U8") (pin "10") (pinfunction "-INA_10") (pintype "input"))
    )
    (net (code "44") (name "Net-(U8--INB)") (class "Default")
      (node (ref "U8") (pin "2") (pinfunction "OUTB_2") (pintype "output"))
      (node (ref "U8") (pin "7") (pinfunction "-INB_7") (pintype "input"))
    )
    (net (code "45") (name "Net-(U8-OUTA)") (class "Default")
      (node (ref "J8") (pin "1") (pinfunction "1_1") (pintype "passive"))
      (node (ref "R20") (pin "2") (pinfunction "2_2") (pintype "passive"))
      (node (ref "U8") (pin "16") (pinfunction "OUTA_16") (pintype "output"))
    )
    (net (code "46") (name "Net-(U10-RB4{slash}AN10{slash}SDI{slash}SDA)") (class "Default")
      (node (ref "R30") (pin "1") (pinfunction "1_1") (pintype "passive"))
      (node (ref "U10") (pin "13") (pinfunction "RB4/AN10/SDI/SDA_13") (pintype "bidirectional"))
    )
    (net (code "47") (name "Net-(U11-3V3OUT)") (class "Default")
      (node (ref "C24") (pin "1") (pinfunction "1_1") (pintype "passive"))
      (node (ref "U11") (pin "13") (pinfunction "3V3OUT_13") (pintype "bidirectional"))
      (node (ref "U11") (pin "14") (pinfunction "~{RESET}_14") (pintype "bidirectional"))
      (node (ref "U11") (pin "3") (pinfunction "VCCIO_3") (pintype "bidirectional"))
    )
    (net (code "48") (name "Net-(U11-TXD)") (class "Default")
      (node (ref "D1") (pin "C") (pinfunction "C_C") (pintype "passive"))
      (node (ref "U11") (pin "20") (pinfunction "TXD_20") (pintype "bidirectional"))
    )
    (net (code "49") (name "Net-(USB-VBUS)") (class "Default")
      (node (ref "R26") (pin "2") (pinfunction "2_2") (pintype "passive"))
      (node (ref "USB") (pin "VUSB") (pinfunction "VBUS_VUSB") (pintype "bidirectional"))
    )
    (net (code "50") (name "PIN0") (class "Default")
      (node (ref "R9") (pin "1") (pinfunction "1_1") (pintype "passive"))
      (node (ref "U10") (pin "9") (pinfunction "RC7/AN9/SDO_9") (pintype "bidirectional"))
    )
    (net (code "51") (name "PIN1") (class "Default")
      (node (ref "R10") (pin "1") (pinfunction "1_1") (pintype "passive"))
      (node (ref "U10") (pin "8") (pinfunction "RC6/AN8/~{SS}_8") (pintype "bidirectional"))
    )
    (net (code "52") (name "PIN2") (class "Default")
      (node (ref "R11") (pin "1") (pinfunction "1_1") (pintype "passive"))
      (node (ref "U10") (pin "5") (pinfunction "RC5/CCP1_5") (pintype "bidirectional"))
    )
    (net (code "53") (name "PIN3") (class "Default")
      (node (ref "R12") (pin "1") (pinfunction "1_1") (pintype "passive"))
      (node (ref "U10") (pin "6") (pinfunction "RC4_6") (pintype "bidirectional"))
    )
    (net (code "54") (name "PIN4") (class "Default")
      (node (ref "R21") (pin "1") (pinfunction "1_1") (pintype "passive"))
      (node (ref "U10") (pin "7") (pinfunction "RC3/AN7_7") (pintype "bidirectional"))
    )
    (net (code "55") (name "PIN5") (class "Default")
      (node (ref "R22") (pin "1") (pinfunction "1_1") (pintype "passive"))
      (node (ref "U10") (pin "14") (pinfunction "RC2/AN6_14") (pintype "bidirectional"))
    )
    (net (code "56") (name "PIN6") (class "Default")
      (node (ref "R23") (pin "1") (pinfunction "1_1") (pintype "passive"))
      (node (ref "U10") (pin "15") (pinfunction "RC1/AN5_15") (pintype "bidirectional"))
    )
    (net (code "57") (name "PIN7") (class "Default")
      (node (ref "R24") (pin "1") (pinfunction "1_1") (pintype "passive"))
      (node (ref "U10") (pin "16") (pinfunction "RC0/AN4_16") (pintype "bidirectional"))
    )
    (net (code "58") (name "TO_USB") (class "Default")
      (node (ref "U10") (pin "10") (pinfunction "RB7/TX/CK_10") (pintype "bidirectional"))
      (node (ref "U11") (pin "4") (pinfunction "RXD_4") (pintype "bidirectional"))
    )
    (net (code "59") (name "USBDM") (class "Default")
      (node (ref "R25") (pin "2") (pinfunction "2_2") (pintype "passive"))
      (node (ref "U11") (pin "12") (pinfunction "USBDM_12") (pintype "bidirectional"))
    )
    (net (code "60") (name "USBDP") (class "Default")
      (node (ref "R27") (pin "2") (pinfunction "2_2") (pintype "passive"))
      (node (ref "U11") (pin "11") (pinfunction "USBDP_11") (pintype "bidirectional"))
    )
    (net (code "61") (name "VBUS_SENSE") (class "Default")
      (node (ref "R26") (pin "1") (pinfunction "1_1") (pintype "passive"))
      (node (ref "R28") (pin "2") (pinfunction "2_2") (pintype "passive"))
      (node (ref "U11") (pin "18") (pinfunction "CBUS0_18") (pintype "bidirectional"))
    )
    (net (code "62") (name "VCC") (class "Default")
      (node (ref "15VDC") (pin "VIN0") (pinfunction "PWR_VIN0") (pintype "bidirectional"))
      (node (ref "C1") (pin "1") (pinfunction "1_1") (pintype "passive"))
      (node (ref "C10") (pin "1") (pinfunction "1_1") (pintype "passive"))
      (node (ref "C11") (pin "1") (pinfunction "1_1") (pintype "passive"))
      (node (ref "C12") (pin "1") (pinfunction "1_1") (pintype "passive"))
      (node (ref "C19") (pin "1") (pinfunction "1_1") (pintype "passive"))
      (node (ref "C2") (pin "1") (pinfunction "1_1") (pintype "passive"))
      (node (ref "C3") (pin "1") (pinfunction "1_1") (pintype "passive"))
      (node (ref "C4") (pin "1") (pinfunction "1_1") (pintype "passive"))
      (node (ref "C9") (pin "1") (pinfunction "1_1") (pintype "passive"))
      (node (ref "U1") (pin "1") (pinfunction "VCC_1") (pintype "power_in"))
      (node (ref "U2") (pin "1") (pinfunction "VCC_1") (pintype "power_in"))
      (node (ref "U3") (pin "1") (pinfunction "VCC_1") (pintype "power_in"))
      (node (ref "U4") (pin "1") (pinfunction "VCC_1") (pintype "power_in"))
      (node (ref "U5") (pin "1") (pinfunction "VCC_1") (pintype "power_in"))
      (node (ref "U6") (pin "1") (pinfunction "VCC_1") (pintype "power_in"))
      (node (ref "U7") (pin "1") (pinfunction "VCC_1") (pintype "power_in"))
      (node (ref "U8") (pin "1") (pinfunction "VCC_1") (pintype "power_in"))
      (node (ref "U9") (pin "3") (pinfunction "VI_3") (pintype "input"))
    )
    (net (code "63") (name "unconnected-(PROGRAM-Pad6)") (class "Default")
      (node (ref "PROGRAM") (pin "6") (pinfunction "6_6") (pintype "bidirectional"))
    )
    (net (code "64") (name "unconnected-(U10-RA2{slash}AN2{slash}T0CKI{slash}INT-Pad17)") (class "Default")
      (node (ref "U10") (pin "17") (pinfunction "RA2/AN2/T0CKI/INT_17") (pintype "bidirectional"))
    )
    (net (code "65") (name "unconnected-(U10-RA4{slash}AN3{slash}~{T1G{slash}}CLKOUT-Pad3)") (class "Default")
      (node (ref "U10") (pin "3") (pinfunction "RA4/AN3/~{T1G/}CLKOUT_3") (pintype "bidirectional"))
    )
    (net (code "66") (name "unconnected-(U10-RA5{slash}T1CKI{slash}CLKIN-Pad2)") (class "Default")
      (node (ref "U10") (pin "2") (pinfunction "RA5/T1CKI/CLKIN_2") (pintype "input"))
    )
    (net (code "67") (name "unconnected-(U10-RB6?SCK{slash}SCL-Pad11)") (class "Default")
      (node (ref "U10") (pin "11") (pinfunction "RB6?SCK/SCL_11") (pintype "bidirectional"))
    )
    (net (code "68") (name "unconnected-(U11-CBUS1-Pad17)") (class "Default")
      (node (ref "U11") (pin "17") (pinfunction "CBUS1_17") (pintype "bidirectional"))
    )
    (net (code "69") (name "unconnected-(U11-CBUS2-Pad10)") (class "Default")
      (node (ref "U11") (pin "10") (pinfunction "CBUS2_10") (pintype "bidirectional"))
    )
    (net (code "70") (name "unconnected-(U11-CBUS3-Pad19)") (class "Default")
      (node (ref "U11") (pin "19") (pinfunction "CBUS3_19") (pintype "bidirectional"))
    )
    (net (code "71") (name "unconnected-(U11-~{CTS}-Pad9)") (class "Default")
      (node (ref "U11") (pin "9") (pinfunction "~{CTS}_9") (pintype "bidirectional"))
    )
    (net (code "72") (name "unconnected-(U11-~{DCD}-Pad8)") (class "Default")
      (node (ref "U11") (pin "8") (pinfunction "~{DCD}_8") (pintype "bidirectional"))
    )
    (net (code "73") (name "unconnected-(U11-~{DSR}-Pad7)") (class "Default")
      (node (ref "U11") (pin "7") (pinfunction "~{DSR}_7") (pintype "bidirectional"))
    )
    (net (code "74") (name "unconnected-(U11-~{DTR}-Pad1)") (class "Default")
      (node (ref "U11") (pin "1") (pinfunction "~{DTR}_1") (pintype "bidirectional"))
    )
    (net (code "75") (name "unconnected-(U11-~{RI}-Pad5)") (class "Default")
      (node (ref "U11") (pin "5") (pinfunction "~{RI}_5") (pintype "bidirectional"))
    )
    (net (code "76") (name "unconnected-(U11-~{RTS}-Pad2)") (class "Default")
      (node (ref "U11") (pin "2") (pinfunction "~{RTS}_2") (pintype "bidirectional"))
    )
  )
)
